# 10_TF_Card.net
KiCad netlist of a schematic drawn in Altium Designer
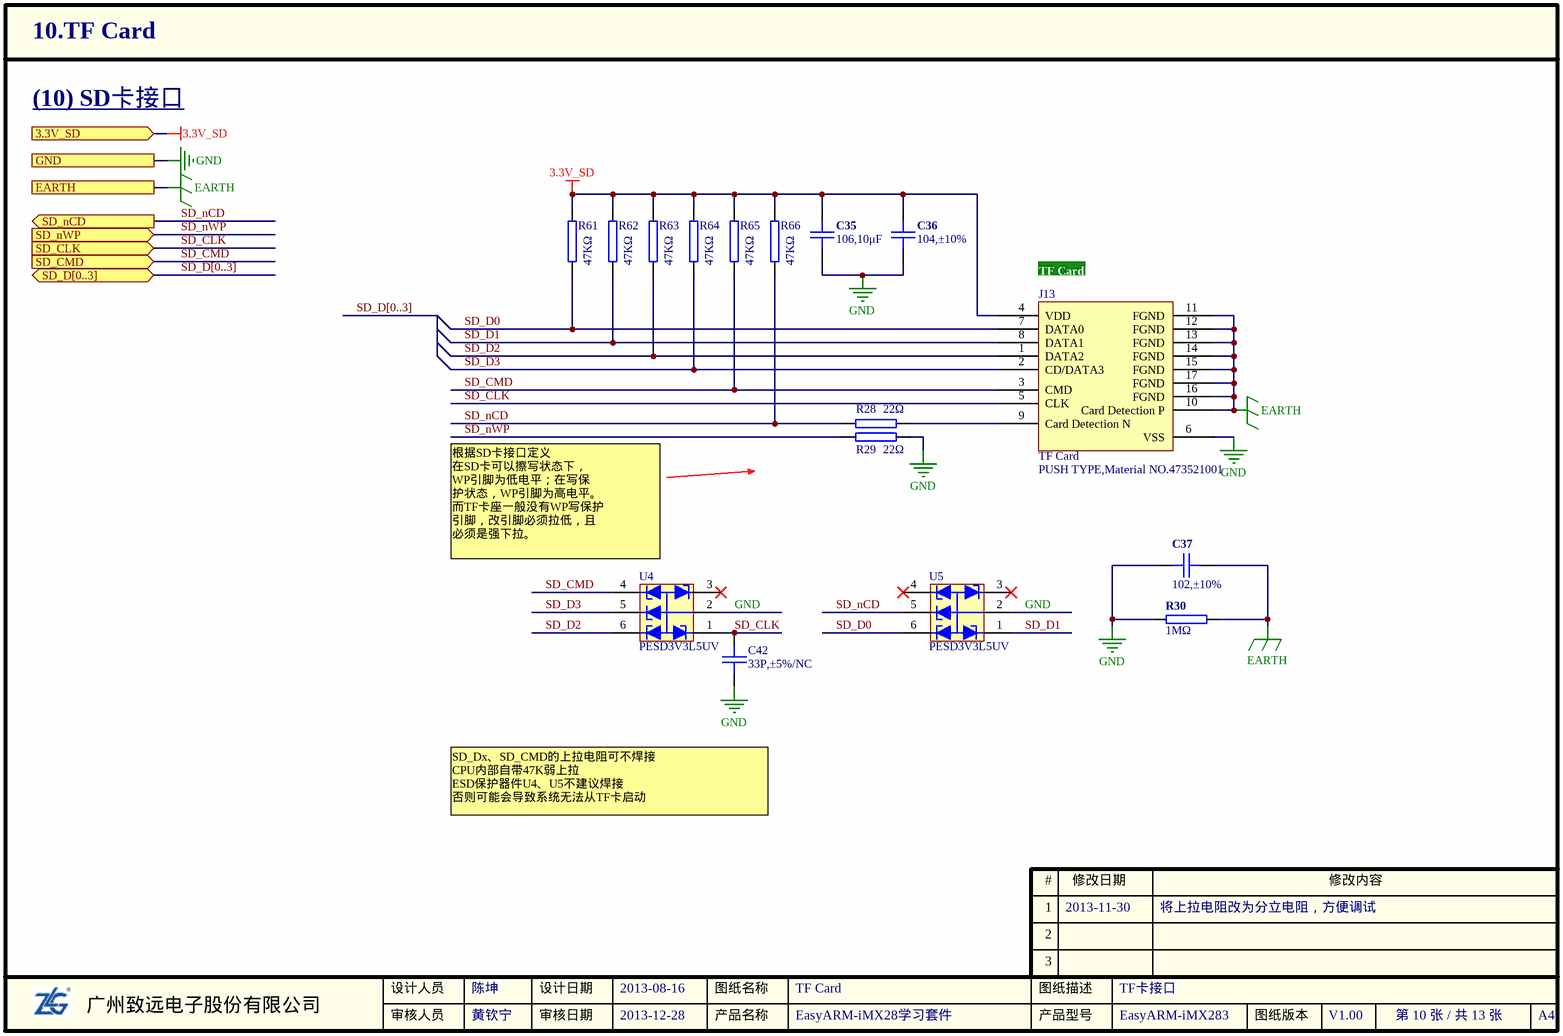
[diagram p0: 10. TF Card.SchDoc]

(export (version "E")
  (design (tool "Eeschema 10.0.6"))
  (components
    (comp (ref "C35")
      (value "106,10μF")
      (footprint "0805C")
      (description "106,10μF,±10%,10V,X5R,0805,RoHS")
      (libsource (lib "ErpMaterialData") (part "CAP1"))
    )
    (comp (ref "C36")
      (value "104,±10%")
      (footprint "0603C")
      (description "104,±10%,50V,X7R,0603,*,RoHS")
      (libsource (lib "ErpMaterialData") (part "CAP1"))
    )
    (comp (ref "C37")
      (value "102,±10%")
      (footprint "1206C")
      (description "Capacitor")
      (libsource (lib "ErpMaterialData") (part "CAP1"))
    )
    (comp (ref "C42")
      (value "33P,±5%/NC")
      (footprint "0603C")
      (description "33P,±5%,50V,COG,0603,RoHS")
      (libsource (lib "ErpMaterialData") (part "CAP1"))
    )
    (comp (ref "J13")
      (value "TF Card")
      (footprint "TF-MOLEX_a")
      (description "PUSH TYPE,Material NO.473521001,15.2×14×1.88mm,molex,RoHS")
      (fields (field (name "ALTIUM_VALUE") "PUSH TYPE,Material NO.473521001"))
      (libsource (lib "ErpMaterialData") (part "TF Card"))
    )
    (comp (ref "R28") (value "22Ω") (footprint "0603R") (libsource (lib "ErpMaterialData") (part "RES2")))
    (comp (ref "R29") (value "22Ω") (footprint "0603R") (libsource (lib "ErpMaterialData") (part "RES2")))
    (comp (ref "R30") (value "1MΩ") (footprint "1206R") (libsource (lib "ErpMaterialData") (part "RES2")))
    (comp (ref "R61")
      (value "47KΩ")
      (footprint "0603R")
      (description "47KΩ,0603,*,RoHS")
      (libsource (lib "ErpMaterialData") (part "RES2"))
    )
    (comp (ref "R62")
      (value "47KΩ")
      (footprint "0603R")
      (description "47KΩ,0603,*,RoHS")
      (libsource (lib "ErpMaterialData") (part "RES2"))
    )
    (comp (ref "R63")
      (value "47KΩ")
      (footprint "0603R")
      (description "47KΩ,0603,*,RoHS")
      (libsource (lib "ErpMaterialData") (part "RES2"))
    )
    (comp (ref "R64")
      (value "47KΩ")
      (footprint "0603R")
      (description "47KΩ,0603,*,RoHS")
      (libsource (lib "ErpMaterialData") (part "RES2"))
    )
    (comp (ref "R65")
      (value "47KΩ")
      (footprint "0603R")
      (description "47KΩ,0603,*,RoHS")
      (libsource (lib "ErpMaterialData") (part "RES2"))
    )
    (comp (ref "R66")
      (value "47KΩ")
      (footprint "0603R")
      (description "47KΩ,0603,*,RoHS")
      (libsource (lib "ErpMaterialData") (part "RES2"))
    )
    (comp (ref "U4")
      (value "PESD3V3L5UV")
      (footprint "SOT-666")
      (description "PESD3V3L5UV,SOT-666,NXP,RoHS")
      (fields (field (name "Comment") "PESD5V0L5UV"))
      (libsource (lib "ErpMaterialData") (part "PESD5V0L5UV"))
    )
    (comp (ref "U5")
      (value "PESD3V3L5UV")
      (footprint "SOT-666")
      (description "PESD3V3L5UV,SOT-666,NXP,RoHS")
      (fields (field (name "Comment") "PESD5V0L5UV"))
      (libsource (lib "ErpMaterialData") (part "PESD5V0L5UV"))
    )
  )
  (nets
    (net (code "1") (name "/SD_CLK") (class "Default")
      (node (ref "C42") (pin "1") (pinfunction "1_1") (pintype "passive"))
      (node (ref "J13") (pin "5") (pinfunction "CLK_5") (pintype "passive"))
      (node (ref "U4") (pin "1") (pintype "passive"))
    )
    (net (code "2") (name "/SD_CMD") (class "Default")
      (node (ref "J13") (pin "3") (pinfunction "CMD_3") (pintype "passive"))
      (node (ref "R65") (pin "1") (pinfunction "1_1") (pintype "passive"))
      (node (ref "U4") (pin "4") (pintype "passive"))
    )
    (net (code "3") (name "/SD_D0") (class "Default")
      (node (ref "J13") (pin "7") (pinfunction "DATA0_7") (pintype "passive"))
      (node (ref "R61") (pin "1") (pinfunction "1_1") (pintype "passive"))
      (node (ref "U5") (pin "6") (pintype "passive"))
    )
    (net (code "4") (name "/SD_D1") (class "Default")
      (node (ref "J13") (pin "8") (pinfunction "DATA1_8") (pintype "passive"))
      (node (ref "R62") (pin "1") (pinfunction "1_1") (pintype "passive"))
      (node (ref "U5") (pin "1") (pintype "passive"))
    )
    (net (code "5") (name "/SD_D2") (class "Default")
      (node (ref "J13") (pin "1") (pinfunction "DATA2_1") (pintype "passive"))
      (node (ref "R63") (pin "1") (pinfunction "1_1") (pintype "passive"))
      (node (ref "U4") (pin "6") (pintype "passive"))
    )
    (net (code "6") (name "/SD_D3") (class "Default")
      (node (ref "J13") (pin "2") (pinfunction "CD/DATA3_2") (pintype "passive"))
      (node (ref "R64") (pin "1") (pinfunction "1_1") (pintype "passive"))
      (node (ref "U4") (pin "5") (pintype "passive"))
    )
    (net (code "8") (name "/SD_nCD") (class "Default")
      (node (ref "R28") (pin "1") (pinfunction "1_1") (pintype "passive"))
      (node (ref "R66") (pin "1") (pinfunction "1_1") (pintype "passive"))
      (node (ref "U5") (pin "5") (pintype "passive"))
    )
    (net (code "9") (name "/SD_nWP") (class "Default")
      (node (ref "R29") (pin "2") (pinfunction "2_2") (pintype "passive"))
    )
    (net (code "10") (name "3.3V_SD") (class "Default")
      (node (ref "C35") (pin "1") (pinfunction "1_1") (pintype "passive"))
      (node (ref "C36") (pin "1") (pinfunction "1_1") (pintype "passive"))
      (node (ref "J13") (pin "4") (pinfunction "VDD_4") (pintype "passive"))
      (node (ref "R61") (pin "2") (pinfunction "2_2") (pintype "passive"))
      (node (ref "R62") (pin "2") (pinfunction "2_2") (pintype "passive"))
      (node (ref "R63") (pin "2") (pinfunction "2_2") (pintype "passive"))
      (node (ref "R64") (pin "2") (pinfunction "2_2") (pintype "passive"))
      (node (ref "R65") (pin "2") (pinfunction "2_2") (pintype "passive"))
      (node (ref "R66") (pin "2") (pinfunction "2_2") (pintype "passive"))
    )
    (net (code "11") (name "EARTH") (class "Default")
      (node (ref "C37") (pin "1") (pinfunction "1_1") (pintype "passive"))
      (node (ref "J13") (pin "10") (pinfunction "Card_Detection_P_10") (pintype "passive"))
      (node (ref "J13") (pin "11") (pinfunction "FGND_11") (pintype "passive"))
      (node (ref "J13") (pin "12") (pinfunction "FGND_12") (pintype "passive"))
      (node (ref "J13") (pin "13") (pinfunction "FGND_13") (pintype "passive"))
      (node (ref "J13") (pin "14") (pinfunction "FGND_14") (pintype "passive"))
      (node (ref "J13") (pin "15") (pinfunction "FGND_15") (pintype "passive"))
      (node (ref "J13") (pin "16") (pinfunction "FGND_16") (pintype "passive"))
      (node (ref "J13") (pin "17") (pinfunction "FGND_17") (pintype "passive"))
      (node (ref "R30") (pin "1") (pinfunction "1_1") (pintype "passive"))
    )
    (net (code "12") (name "GND") (class "Default")
      (node (ref "C35") (pin "2") (pinfunction "2_2") (pintype "passive"))
      (node (ref "C36") (pin "2") (pinfunction "2_2") (pintype "passive"))
      (node (ref "C37") (pin "2") (pinfunction "2_2") (pintype "passive"))
      (node (ref "C42") (pin "2") (pinfunction "2_2") (pintype "passive"))
      (node (ref "J13") (pin "6") (pinfunction "VSS_6") (pintype "passive"))
      (node (ref "R29") (pin "1") (pinfunction "1_1") (pintype "passive"))
      (node (ref "R30") (pin "2") (pinfunction "2_2") (pintype "passive"))
      (node (ref "U4") (pin "2") (pintype "passive"))
      (node (ref "U5") (pin "2") (pintype "passive"))
    )
    (net (code "13") (name "Net-(J13-Card_Detection_N)") (class "Default")
      (node (ref "J13") (pin "9") (pinfunction "Card_Detection_N_9") (pintype "passive"))
      (node (ref "R28") (pin "2") (pinfunction "2_2") (pintype "passive"))
    )
    (net (code "14") (name "unconnected-(U4-Pad3)") (class "Default")
      (node (ref "U4") (pin "3") (pintype "passive+no_connect"))
    )
    (net (code "15") (name "unconnected-(U5-Pad3)") (class "Default")
      (node (ref "U5") (pin "3") (pintype "passive+no_connect"))
    )
    (net (code "16") (name "unconnected-(U5-Pad4)") (class "Default")
      (node (ref "U5") (pin "4") (pintype "passive+no_connect"))
    )
  )
)
